# solenoid_final.net
KiCad netlist of a schematic drawn in EAGLE
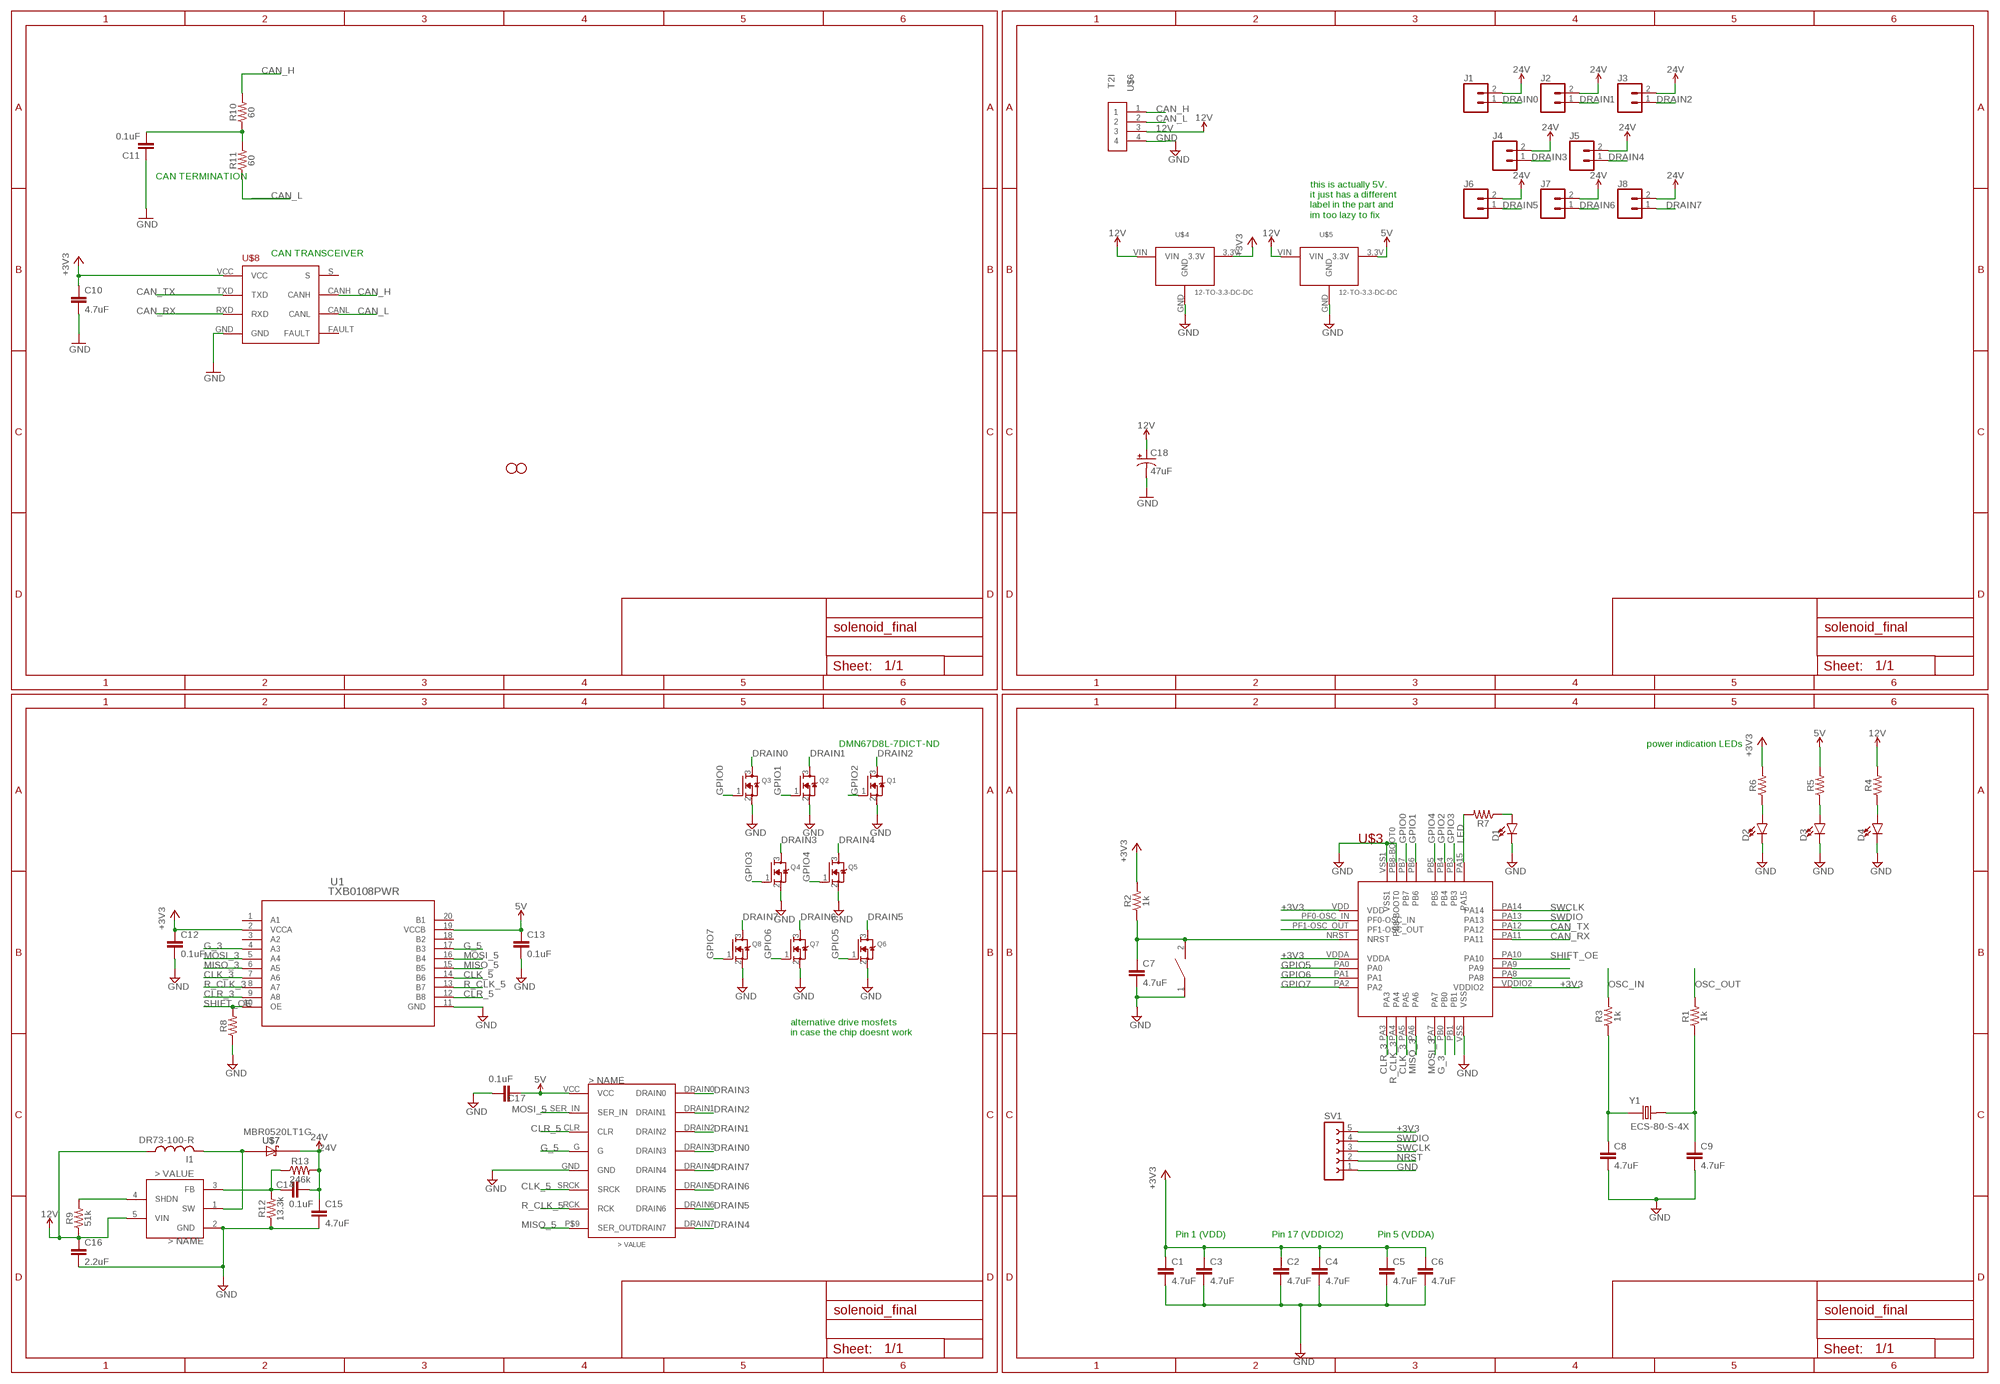
[diagram p0: schematic, sheet 1]

(export (version "E")
  (design (tool "Eeschema 10.0.6"))
  (components
    (comp (ref "C1")
      (value "4.7uF")
      (footprint "eagle-import:0603")
      (libsource (lib "eagle-import") (part "4.7UF0603"))
    )
    (comp (ref "C2")
      (value "4.7uF")
      (footprint "eagle-import:0603")
      (libsource (lib "eagle-import") (part "4.7UF0603"))
    )
    (comp (ref "C3")
      (value "4.7uF")
      (footprint "eagle-import:0603")
      (libsource (lib "eagle-import") (part "4.7UF0603"))
    )
    (comp (ref "C4")
      (value "4.7uF")
      (footprint "eagle-import:0603")
      (libsource (lib "eagle-import") (part "4.7UF0603"))
    )
    (comp (ref "C5")
      (value "4.7uF")
      (footprint "eagle-import:0603")
      (libsource (lib "eagle-import") (part "4.7UF0603"))
    )
    (comp (ref "C6")
      (value "4.7uF")
      (footprint "eagle-import:0603")
      (libsource (lib "eagle-import") (part "4.7UF0603"))
    )
    (comp (ref "C7")
      (value "4.7uF")
      (footprint "eagle-import:0603")
      (libsource (lib "eagle-import") (part "4.7UF0603"))
    )
    (comp (ref "C8")
      (value "4.7uF")
      (footprint "eagle-import:0603")
      (libsource (lib "eagle-import") (part "4.7UF0603"))
    )
    (comp (ref "C9")
      (value "4.7uF")
      (footprint "eagle-import:0603")
      (libsource (lib "eagle-import") (part "4.7UF0603"))
    )
    (comp (ref "C10")
      (value "4.7uF")
      (footprint "eagle-import:0603")
      (libsource (lib "eagle-import") (part "4.7UF0603"))
    )
    (comp (ref "C11")
      (value "0.1uF")
      (footprint "eagle-import:0603")
      (libsource (lib "eagle-import") (part "0.1UF-0603-25V-(+80/-20%)"))
    )
    (comp (ref "C12")
      (value "0.1uF")
      (footprint "eagle-import:0603")
      (libsource (lib "eagle-import") (part "0.1UF-0603-25V-5%"))
    )
    (comp (ref "C13")
      (value "0.1uF")
      (footprint "eagle-import:0603")
      (libsource (lib "eagle-import") (part "0.1UF-0603-25V-5%"))
    )
    (comp (ref "C14")
      (value "0.1uF")
      (footprint "eagle-import:0603")
      (libsource (lib "eagle-import") (part "0.1UF-0603-25V-5%"))
    )
    (comp (ref "C15")
      (value "4.7uF")
      (footprint "eagle-import:0603")
      (libsource (lib "eagle-import") (part "0.1UF-0603-25V-5%"))
    )
    (comp (ref "C16")
      (value "2.2uF")
      (footprint "eagle-import:0603")
      (libsource (lib "eagle-import") (part "0.1UF-0603-25V-5%"))
    )
    (comp (ref "C17")
      (value "0.1uF")
      (footprint "eagle-import:0603")
      (libsource (lib "eagle-import") (part "0.1UF-0603-25V-5%"))
    )
    (comp (ref "C18")
      (value "47uF")
      (footprint "eagle-import:PANASONIC_D")
      (libsource (lib "eagle-import") (part "47UF-POLAR-PANASONIC_D-35V-20%"))
    )
    (comp (ref "D1")
      (value "LED0603")
      (footprint "eagle-import:LED-0603")
      (libsource (lib "eagle-import") (part "LED0603"))
    )
    (comp (ref "D2")
      (value "LED0603")
      (footprint "eagle-import:LED-0603")
      (libsource (lib "eagle-import") (part "LED0603"))
    )
    (comp (ref "D3")
      (value "LED0603")
      (footprint "eagle-import:LED-0603")
      (libsource (lib "eagle-import") (part "LED0603"))
    )
    (comp (ref "D4")
      (value "LED0603")
      (footprint "eagle-import:LED-0603")
      (libsource (lib "eagle-import") (part "LED0603"))
    )
    (comp (ref "H1")
      (value "STAND-OFF")
      (footprint "eagle-import:STAND-OFF")
      (libsource (lib "eagle-import") (part "STAND-OFF"))
    )
    (comp (ref "H2")
      (value "STAND-OFF")
      (footprint "eagle-import:STAND-OFF")
      (libsource (lib "eagle-import") (part "STAND-OFF"))
    )
    (comp (ref "I1")
      (value "DR73-100-R")
      (footprint "eagle-import:DR73-100-R")
      (libsource (lib "eagle-import") (part "DR73-100-R"))
    )
    (comp (ref "J1")
      (value "CONN_02")
      (footprint "eagle-import:1X02")
      (libsource (lib "eagle-import") (part "CONN_02"))
    )
    (comp (ref "J2")
      (value "CONN_02")
      (footprint "eagle-import:1X02")
      (libsource (lib "eagle-import") (part "CONN_02"))
    )
    (comp (ref "J3")
      (value "CONN_02")
      (footprint "eagle-import:1X02")
      (libsource (lib "eagle-import") (part "CONN_02"))
    )
    (comp (ref "J4")
      (value "CONN_02")
      (footprint "eagle-import:1X02")
      (libsource (lib "eagle-import") (part "CONN_02"))
    )
    (comp (ref "J5")
      (value "CONN_02")
      (footprint "eagle-import:1X02")
      (libsource (lib "eagle-import") (part "CONN_02"))
    )
    (comp (ref "J6")
      (value "CONN_02")
      (footprint "eagle-import:1X02")
      (libsource (lib "eagle-import") (part "CONN_02"))
    )
    (comp (ref "J7")
      (value "CONN_02")
      (footprint "eagle-import:1X02")
      (libsource (lib "eagle-import") (part "CONN_02"))
    )
    (comp (ref "J8")
      (value "CONN_02")
      (footprint "eagle-import:1X02")
      (libsource (lib "eagle-import") (part "CONN_02"))
    )
    (comp (ref "Q1")
      (value "MOSFET-NWIDE")
      (footprint "eagle-import:SOT23-WIDE")
      (libsource (lib "eagle-import") (part "MOSFET-NWIDE"))
    )
    (comp (ref "Q2")
      (value "MOSFET-NWIDE")
      (footprint "eagle-import:SOT23-WIDE")
      (libsource (lib "eagle-import") (part "MOSFET-NWIDE"))
    )
    (comp (ref "Q3")
      (value "MOSFET-NWIDE")
      (footprint "eagle-import:SOT23-WIDE")
      (libsource (lib "eagle-import") (part "MOSFET-NWIDE"))
    )
    (comp (ref "Q4")
      (value "MOSFET-NWIDE")
      (footprint "eagle-import:SOT23-WIDE")
      (libsource (lib "eagle-import") (part "MOSFET-NWIDE"))
    )
    (comp (ref "Q5")
      (value "MOSFET-NWIDE")
      (footprint "eagle-import:SOT23-WIDE")
      (libsource (lib "eagle-import") (part "MOSFET-NWIDE"))
    )
    (comp (ref "Q6")
      (value "MOSFET-NWIDE")
      (footprint "eagle-import:SOT23-WIDE")
      (libsource (lib "eagle-import") (part "MOSFET-NWIDE"))
    )
    (comp (ref "Q7")
      (value "MOSFET-NWIDE")
      (footprint "eagle-import:SOT23-WIDE")
      (libsource (lib "eagle-import") (part "MOSFET-NWIDE"))
    )
    (comp (ref "Q8")
      (value "MOSFET-NWIDE")
      (footprint "eagle-import:SOT23-WIDE")
      (libsource (lib "eagle-import") (part "MOSFET-NWIDE"))
    )
    (comp (ref "R1")
      (value "1k")
      (footprint "eagle-import:0603")
      (libsource (lib "eagle-import") (part "1KOHM-0603-1/10W-1%"))
    )
    (comp (ref "R2")
      (value "1k")
      (footprint "eagle-import:0603")
      (libsource (lib "eagle-import") (part "1KOHM-0603-1/10W-1%"))
    )
    (comp (ref "R3")
      (value "1k")
      (footprint "eagle-import:0603")
      (libsource (lib "eagle-import") (part "1KOHM-0603-1/10W-1%"))
    )
    (comp (ref "R4")
      (value "RESISTOR0603")
      (footprint "eagle-import:0603")
      (libsource (lib "eagle-import") (part "RESISTOR0603"))
    )
    (comp (ref "R5")
      (value "RESISTOR0603")
      (footprint "eagle-import:0603")
      (libsource (lib "eagle-import") (part "RESISTOR0603"))
    )
    (comp (ref "R6")
      (value "RESISTOR0603")
      (footprint "eagle-import:0603")
      (libsource (lib "eagle-import") (part "RESISTOR0603"))
    )
    (comp (ref "R7")
      (value "RESISTOR0603")
      (footprint "eagle-import:0603")
      (libsource (lib "eagle-import") (part "RESISTOR0603"))
    )
    (comp (ref "R8")
      (value "RESISTOR0603")
      (footprint "eagle-import:0603")
      (libsource (lib "eagle-import") (part "RESISTOR0603"))
    )
    (comp (ref "R9")
      (value "51k")
      (footprint "eagle-import:0603")
      (libsource (lib "eagle-import") (part "RESISTOR0603"))
    )
    (comp (ref "R10")
      (value "60")
      (footprint "eagle-import:0603")
      (libsource (lib "eagle-import") (part "1KOHM-0603-1/10W-1%"))
    )
    (comp (ref "R11")
      (value "60")
      (footprint "eagle-import:0603")
      (libsource (lib "eagle-import") (part "1KOHM-0603-1/10W-1%"))
    )
    (comp (ref "R12")
      (value "13.3k")
      (footprint "eagle-import:0603")
      (libsource (lib "eagle-import") (part "RESISTOR0603"))
    )
    (comp (ref "R13")
      (value "246k")
      (footprint "eagle-import:0603")
      (libsource (lib "eagle-import") (part "RESISTOR0603"))
    )
    (comp (ref "RESET")
      (value "SWITCH")
      (footprint "eagle-import:SW_2512")
      (libsource (lib "eagle-import") (part "SWITCH"))
    )
    (comp (ref "SV1")
      (value "FE05-1")
      (footprint "eagle-import:FE05-1")
      (libsource (lib "eagle-import") (part "FE05-1"))
    )
    (comp (ref "U$1")
      (value "SHIFT_REGISTER")
      (footprint "eagle-import:SHIFT_REGISTER")
      (libsource (lib "eagle-import") (part "SHIFT_REGISTER"))
    )
    (comp (ref "U$2")
      (value "LM27313")
      (footprint "eagle-import:SOT95P300X145-5")
      (libsource (lib "eagle-import") (part "LM27313"))
    )
    (comp (ref "U$3")
      (value "STM32F042K6T6")
      (footprint "eagle-import:STM32F042K6T6")
      (libsource (lib "eagle-import") (part "STM32F042K6T6"))
    )
    (comp (ref "U$4")
      (value "12-TO-3.3-DC-DC")
      (footprint "eagle-import:MURATA-DCDC")
      (libsource (lib "eagle-import") (part "12-TO-3.3-DC-DC"))
    )
    (comp (ref "U$5")
      (value "12-TO-3.3-DC-DC")
      (footprint "eagle-import:MURATA-DCDC")
      (libsource (lib "eagle-import") (part "12-TO-3.3-DC-DC"))
    )
    (comp (ref "U$6")
      (value "T2I")
      (footprint "eagle-import:T2I")
      (libsource (lib "eagle-import") (part "T2I"))
    )
    (comp (ref "U$7")
      (value "MBR0520LT1G")
      (footprint "eagle-import:SOD3716X135")
      (libsource (lib "eagle-import") (part "MBR0520LT1G"))
    )
    (comp (ref "U$8")
      (value "TCAN337D")
      (footprint "eagle-import:TCAN337D")
      (libsource (lib "eagle-import") (part "TCAN337D"))
    )
    (comp (ref "U1")
      (value "TXB0108PWR")
      (footprint "eagle-import:PW20")
      (libsource (lib "eagle-import") (part "TXB0108PWR"))
    )
    (comp (ref "Y1")
      (value "ECS-80-S-4X")
      (footprint "eagle-import:XTAL_ECS-80-S-4X")
      (fields (field (name "DIGI-KEY_PART_NUMBER") "X1057-ND") (field (name "MF") "ECS International"))
      (libsource (lib "eagle-import") (part "ECS-80-S-4X"))
    )
  )
  (nets
    (net (code "1") (name "+3V3") (class "Default")
      (node (ref "C1") (pin "1") (pinfunction "1_1") (pintype "passive"))
      (node (ref "C10") (pin "1") (pinfunction "1_1") (pintype "passive"))
      (node (ref "C12") (pin "1") (pinfunction "1_1") (pintype "passive"))
      (node (ref "C2") (pin "1") (pinfunction "1_1") (pintype "passive"))
      (node (ref "C3") (pin "1") (pinfunction "1_1") (pintype "passive"))
      (node (ref "C4") (pin "1") (pinfunction "1_1") (pintype "passive"))
      (node (ref "C5") (pin "1") (pinfunction "1_1") (pintype "passive"))
      (node (ref "C6") (pin "1") (pinfunction "1_1") (pintype "passive"))
      (node (ref "R2") (pin "2") (pinfunction "2_2") (pintype "passive"))
      (node (ref "R6") (pin "2") (pinfunction "2_2") (pintype "passive"))
      (node (ref "SV1") (pin "5") (pinfunction "5_5") (pintype "passive"))
      (node (ref "U$3") (pin "VDD") (pinfunction "VDD_VDD") (pintype "bidirectional"))
      (node (ref "U$3") (pin "VDDA") (pinfunction "VDDA_VDDA") (pintype "bidirectional"))
      (node (ref "U$3") (pin "VDDIO2") (pinfunction "VDDIO2_VDDIO2") (pintype "bidirectional"))
      (node (ref "U$4") (pin "3.3V") (pinfunction "3.3V_3.3V") (pintype "bidirectional"))
      (node (ref "U$8") (pin "VCC") (pinfunction "VCC_VCC") (pintype "bidirectional"))
      (node (ref "U1") (pin "2") (pinfunction "VCCA_2") (pintype "power_in"))
    )
    (net (code "2") (name "/CAN_H") (class "Default")
      (node (ref "R10") (pin "2") (pinfunction "2_2") (pintype "passive"))
      (node (ref "U$6") (pin "1") (pinfunction "1_1") (pintype "bidirectional"))
      (node (ref "U$8") (pin "CANH") (pinfunction "CANH_CANH") (pintype "bidirectional"))
    )
    (net (code "3") (name "/CAN_L") (class "Default")
      (node (ref "R11") (pin "1") (pinfunction "1_1") (pintype "passive"))
      (node (ref "U$6") (pin "2") (pinfunction "2_2") (pintype "bidirectional"))
      (node (ref "U$8") (pin "CANL") (pinfunction "CANL_CANL") (pintype "bidirectional"))
    )
    (net (code "4") (name "/CAN_RX") (class "Default")
      (node (ref "U$3") (pin "PA11") (pinfunction "PA11_PA11") (pintype "bidirectional"))
      (node (ref "U$8") (pin "RXD") (pinfunction "RXD_RXD") (pintype "bidirectional"))
    )
    (net (code "5") (name "/CAN_TX") (class "Default")
      (node (ref "U$3") (pin "PA12") (pinfunction "PA12_PA12") (pintype "bidirectional"))
      (node (ref "U$8") (pin "TXD") (pinfunction "TXD_TXD") (pintype "bidirectional"))
    )
    (net (code "6") (name "/CLK_3") (class "Default")
      (node (ref "U$3") (pin "PA5") (pinfunction "PA5_PA5") (pintype "bidirectional"))
      (node (ref "U1") (pin "7") (pinfunction "A6_7") (pintype "bidirectional"))
    )
    (net (code "7") (name "/CLK_5") (class "Default")
      (node (ref "U$1") (pin "SRCK") (pinfunction "SRCK_SRCK") (pintype "bidirectional"))
      (node (ref "U1") (pin "14") (pinfunction "B6_14") (pintype "bidirectional"))
    )
    (net (code "8") (name "/CLR_3") (class "Default")
      (node (ref "U$3") (pin "PA3") (pinfunction "PA3_PA3") (pintype "bidirectional"))
      (node (ref "U1") (pin "9") (pinfunction "A8_9") (pintype "bidirectional"))
    )
    (net (code "9") (name "/CLR_5") (class "Default")
      (node (ref "U$1") (pin "CLR") (pinfunction "CLR_CLR") (pintype "bidirectional"))
      (node (ref "U1") (pin "12") (pinfunction "B8_12") (pintype "bidirectional"))
    )
    (net (code "10") (name "/DRAIN0") (class "Default")
      (node (ref "J1") (pin "1") (pinfunction "1_1") (pintype "passive"))
      (node (ref "Q3") (pin "3") (pinfunction "D_3") (pintype "bidirectional"))
      (node (ref "U$1") (pin "DRAIN3") (pinfunction "DRAIN3_DRAIN3") (pintype "bidirectional"))
    )
    (net (code "11") (name "/DRAIN1") (class "Default")
      (node (ref "J2") (pin "1") (pinfunction "1_1") (pintype "passive"))
      (node (ref "Q2") (pin "3") (pinfunction "D_3") (pintype "bidirectional"))
      (node (ref "U$1") (pin "DRAIN2") (pinfunction "DRAIN2_DRAIN2") (pintype "bidirectional"))
    )
    (net (code "12") (name "/DRAIN2") (class "Default")
      (node (ref "J3") (pin "1") (pinfunction "1_1") (pintype "passive"))
      (node (ref "Q1") (pin "3") (pinfunction "D_3") (pintype "bidirectional"))
      (node (ref "U$1") (pin "DRAIN1") (pinfunction "DRAIN1_DRAIN1") (pintype "bidirectional"))
    )
    (net (code "13") (name "/DRAIN3") (class "Default")
      (node (ref "J4") (pin "1") (pinfunction "1_1") (pintype "passive"))
      (node (ref "Q4") (pin "3") (pinfunction "D_3") (pintype "bidirectional"))
      (node (ref "U$1") (pin "DRAIN0") (pinfunction "DRAIN0_DRAIN0") (pintype "bidirectional"))
    )
    (net (code "14") (name "/DRAIN4") (class "Default")
      (node (ref "J5") (pin "1") (pinfunction "1_1") (pintype "passive"))
      (node (ref "Q5") (pin "3") (pinfunction "D_3") (pintype "bidirectional"))
      (node (ref "U$1") (pin "DRAIN7") (pinfunction "DRAIN7_DRAIN7") (pintype "bidirectional"))
    )
    (net (code "15") (name "/DRAIN5") (class "Default")
      (node (ref "J6") (pin "1") (pinfunction "1_1") (pintype "passive"))
      (node (ref "Q6") (pin "3") (pinfunction "D_3") (pintype "bidirectional"))
      (node (ref "U$1") (pin "DRAIN6") (pinfunction "DRAIN6_DRAIN6") (pintype "bidirectional"))
    )
    (net (code "16") (name "/DRAIN6") (class "Default")
      (node (ref "J7") (pin "1") (pinfunction "1_1") (pintype "passive"))
      (node (ref "Q7") (pin "3") (pinfunction "D_3") (pintype "bidirectional"))
      (node (ref "U$1") (pin "DRAIN5") (pinfunction "DRAIN5_DRAIN5") (pintype "bidirectional"))
    )
    (net (code "17") (name "/DRAIN7") (class "Default")
      (node (ref "J8") (pin "1") (pinfunction "1_1") (pintype "passive"))
      (node (ref "Q8") (pin "3") (pinfunction "D_3") (pintype "bidirectional"))
      (node (ref "U$1") (pin "DRAIN4") (pinfunction "DRAIN4_DRAIN4") (pintype "bidirectional"))
    )
    (net (code "18") (name "/GPIO0") (class "Default")
      (node (ref "Q3") (pin "1") (pinfunction "G_1") (pintype "bidirectional"))
      (node (ref "U$3") (pin "PB7") (pinfunction "PB7_PB7") (pintype "bidirectional"))
    )
    (net (code "19") (name "/GPIO1") (class "Default")
      (node (ref "Q2") (pin "1") (pinfunction "G_1") (pintype "bidirectional"))
      (node (ref "U$3") (pin "PB6") (pinfunction "PB6_PB6") (pintype "bidirectional"))
    )
    (net (code "20") (name "/GPIO2") (class "Default")
      (node (ref "Q1") (pin "1") (pinfunction "G_1") (pintype "bidirectional"))
      (node (ref "U$3") (pin "PB4") (pinfunction "PB4_PB4") (pintype "bidirectional"))
    )
    (net (code "21") (name "/GPIO3") (class "Default")
      (node (ref "Q4") (pin "1") (pinfunction "G_1") (pintype "bidirectional"))
      (node (ref "U$3") (pin "PB3") (pinfunction "PB3_PB3") (pintype "bidirectional"))
    )
    (net (code "22") (name "/GPIO4") (class "Default")
      (node (ref "Q5") (pin "1") (pinfunction "G_1") (pintype "bidirectional"))
      (node (ref "U$3") (pin "PB5") (pinfunction "PB5_PB5") (pintype "bidirectional"))
    )
    (net (code "23") (name "/GPIO5") (class "Default")
      (node (ref "Q6") (pin "1") (pinfunction "G_1") (pintype "bidirectional"))
      (node (ref "U$3") (pin "PA0") (pinfunction "PA0_PA0") (pintype "bidirectional"))
    )
    (net (code "24") (name "/GPIO6") (class "Default")
      (node (ref "Q7") (pin "1") (pinfunction "G_1") (pintype "bidirectional"))
      (node (ref "U$3") (pin "PA1") (pinfunction "PA1_PA1") (pintype "bidirectional"))
    )
    (net (code "25") (name "/GPIO7") (class "Default")
      (node (ref "Q8") (pin "1") (pinfunction "G_1") (pintype "bidirectional"))
      (node (ref "U$3") (pin "PA2") (pinfunction "PA2_PA2") (pintype "bidirectional"))
    )
    (net (code "26") (name "/G_3") (class "Default")
      (node (ref "U$3") (pin "PB0") (pinfunction "PB0_PB0") (pintype "bidirectional"))
      (node (ref "U1") (pin "4") (pinfunction "A3_4") (pintype "bidirectional"))
    )
    (net (code "27") (name "/G_5") (class "Default")
      (node (ref "U$1") (pin "G") (pinfunction "G_G") (pintype "bidirectional"))
      (node (ref "U1") (pin "17") (pinfunction "B3_17") (pintype "bidirectional"))
    )
    (net (code "28") (name "/LED") (class "Default")
      (node (ref "R7") (pin "2") (pinfunction "2_2") (pintype "passive"))
      (node (ref "U$3") (pin "PA15") (pinfunction "PA15_PA15") (pintype "bidirectional"))
    )
    (net (code "29") (name "/MISO_3") (class "Default")
      (node (ref "U$3") (pin "PA6") (pinfunction "PA6_PA6") (pintype "bidirectional"))
      (node (ref "U1") (pin "6") (pinfunction "A5_6") (pintype "bidirectional"))
    )
    (net (code "30") (name "/MISO_5") (class "Default")
      (node (ref "U$1") (pin "P$9") (pinfunction "SER_OUT_P$9") (pintype "bidirectional"))
      (node (ref "U1") (pin "15") (pinfunction "B5_15") (pintype "bidirectional"))
    )
    (net (code "31") (name "/MOSI_3") (class "Default")
      (node (ref "U$3") (pin "PA7") (pinfunction "PA7_PA7") (pintype "bidirectional"))
      (node (ref "U1") (pin "5") (pinfunction "A4_5") (pintype "bidirectional"))
    )
    (net (code "32") (name "/MOSI_5") (class "Default")
      (node (ref "U$1") (pin "SER_IN") (pinfunction "SER_IN_SER_IN") (pintype "bidirectional"))
      (node (ref "U1") (pin "16") (pinfunction "B4_16") (pintype "bidirectional"))
    )
    (net (code "33") (name "/NRST") (class "Default")
      (node (ref "C7") (pin "1") (pinfunction "1_1") (pintype "passive"))
      (node (ref "R2") (pin "1") (pinfunction "1_1") (pintype "passive"))
      (node (ref "RESET") (pin "2") (pinfunction "P$2_2") (pintype "bidirectional"))
      (node (ref "SV1") (pin "2") (pinfunction "2_2") (pintype "passive"))
      (node (ref "U$3") (pin "NRST") (pinfunction "NRST_NRST") (pintype "bidirectional"))
    )
    (net (code "34") (name "/OSC_IN") (class "Default")
      (node (ref "R3") (pin "2") (pinfunction "2_2") (pintype "passive"))
      (node (ref "U$3") (pin "PF0-OSC_IN") (pinfunction "PF0-OSC_IN_PF0-OSC_IN") (pintype "bidirectional"))
    )
    (net (code "35") (name "/OSC_OUT") (class "Default")
      (node (ref "R1") (pin "2") (pinfunction "2_2") (pintype "passive"))
      (node (ref "U$3") (pin "PF1-OSC_OUT") (pinfunction "PF1-OSC_OUT_PF1-OSC_OUT") (pintype "bidirectional"))
    )
    (net (code "36") (name "/R_CLK_3") (class "Default")
      (node (ref "U$3") (pin "PA4") (pinfunction "PA4_PA4") (pintype "bidirectional"))
      (node (ref "U1") (pin "8") (pinfunction "A7_8") (pintype "bidirectional"))
    )
    (net (code "37") (name "/R_CLK_5") (class "Default")
      (node (ref "U$1") (pin "RCK") (pinfunction "RCK_RCK") (pintype "bidirectional"))
      (node (ref "U1") (pin "13") (pinfunction "B7_13") (pintype "bidirectional"))
    )
    (net (code "38") (name "/SHIFT_OE") (class "Default")
      (node (ref "R8") (pin "2") (pinfunction "2_2") (pintype "passive"))
      (node (ref "U$3") (pin "PA10") (pinfunction "PA10_PA10") (pintype "bidirectional"))
      (node (ref "U1") (pin "10") (pinfunction "OE_10") (pintype "bidirectional"))
    )
    (net (code "39") (name "/SWCLK") (class "Default")
      (node (ref "SV1") (pin "3") (pinfunction "3_3") (pintype "passive"))
      (node (ref "U$3") (pin "PA14") (pinfunction "PA14_PA14") (pintype "bidirectional"))
    )
    (net (code "40") (name "/SWDIO") (class "Default")
      (node (ref "SV1") (pin "4") (pinfunction "4_4") (pintype "passive"))
      (node (ref "U$3") (pin "PA13") (pinfunction "PA13_PA13") (pintype "bidirectional"))
    )
    (net (code "41") (name "5V") (class "Default")
      (node (ref "C13") (pin "1") (pinfunction "1_1") (pintype "passive"))
      (node (ref "C17") (pin "1") (pinfunction "1_1") (pintype "passive"))
      (node (ref "R5") (pin "2") (pinfunction "2_2") (pintype "passive"))
      (node (ref "U$1") (pin "VCC") (pinfunction "VCC_VCC") (pintype "bidirectional"))
      (node (ref "U$5") (pin "3.3V") (pinfunction "3.3V_3.3V") (pintype "bidirectional"))
      (node (ref "U1") (pin "19") (pinfunction "VCCB_19") (pintype "power_in"))
    )
    (net (code "42") (name "12V") (class "Default")
      (node (ref "C16") (pin "1") (pinfunction "1_1") (pintype "passive"))
      (node (ref "C18") (pin "+") (pinfunction "+_+") (pintype "passive"))
      (node (ref "I1") (pin "1") (pinfunction "1_1") (pintype "passive"))
      (node (ref "R4") (pin "2") (pinfunction "2_2") (pintype "passive"))
      (node (ref "R9") (pin "1") (pinfunction "1_1") (pintype "passive"))
      (node (ref "U$2") (pin "5") (pinfunction "VIN_5") (pintype "bidirectional"))
      (node (ref "U$4") (pin "VIN") (pinfunction "VIN_VIN") (pintype "bidirectional"))
      (node (ref "U$5") (pin "VIN") (pinfunction "VIN_VIN") (pintype "bidirectional"))
      (node (ref "U$6") (pin "3") (pinfunction "3_3") (pintype "bidirectional"))
    )
    (net (code "43") (name "24V") (class "Default")
      (node (ref "C14") (pin "2") (pinfunction "2_2") (pintype "passive"))
      (node (ref "C15") (pin "1") (pinfunction "1_1") (pintype "passive"))
      (node (ref "J1") (pin "2") (pinfunction "2_2") (pintype "passive"))
      (node (ref "J2") (pin "2") (pinfunction "2_2") (pintype "passive"))
      (node (ref "J3") (pin "2") (pinfunction "2_2") (pintype "passive"))
      (node (ref "J4") (pin "2") (pinfunction "2_2") (pintype "passive"))
      (node (ref "J5") (pin "2") (pinfunction "2_2") (pintype "passive"))
      (node (ref "J6") (pin "2") (pinfunction "2_2") (pintype "passive"))
      (node (ref "J7") (pin "2") (pinfunction "2_2") (pintype "passive"))
      (node (ref "J8") (pin "2") (pinfunction "2_2") (pintype "passive"))
      (node (ref "R13") (pin "2") (pinfunction "2_2") (pintype "passive"))
      (node (ref "U$7") (pin "2") (pinfunction "C_2") (pintype "passive"))
    )
    (net (code "44") (name "GND") (class "Default")
      (node (ref "C1") (pin "2") (pinfunction "2_2") (pintype "passive"))
      (node (ref "C10") (pin "2") (pinfunction "2_2") (pintype "passive"))
      (node (ref "C11") (pin "1") (pinfunction "1_1") (pintype "passive"))
      (node (ref "C12") (pin "2") (pinfunction "2_2") (pintype "passive"))
      (node (ref "C13") (pin "2") (pinfunction "2_2") (pintype "passive"))
      (node (ref "C15") (pin "2") (pinfunction "2_2") (pintype "passive"))
      (node (ref "C16") (pin "2") (pinfunction "2_2") (pintype "passive"))
      (node (ref "C17") (pin "2") (pinfunction "2_2") (pintype "passive"))
      (node (ref "C18") (pin "-") (pinfunction "-_-") (pintype "passive"))
      (node (ref "C2") (pin "2") (pinfunction "2_2") (pintype "passive"))
      (node (ref "C3") (pin "2") (pinfunction "2_2") (pintype "passive"))
      (node (ref "C4") (pin "2") (pinfunction "2_2") (pintype "passive"))
      (node (ref "C5") (pin "2") (pinfunction "2_2") (pintype "passive"))
      (node (ref "C6") (pin "2") (pinfunction "2_2") (pintype "passive"))
      (node (ref "C7") (pin "2") (pinfunction "2_2") (pintype "passive"))
      (node (ref "C8") (pin "2") (pinfunction "2_2") (pintype "passive"))
      (node (ref "C9") (pin "2") (pinfunction "2_2") (pintype "passive"))
      (node (ref "D1") (pin "C") (pinfunction "C_C") (pintype "passive"))
      (node (ref "D2") (pin "C") (pinfunction "C_C") (pintype "passive"))
      (node (ref "D3") (pin "C") (pinfunction "C_C") (pintype "passive"))
      (node (ref "D4") (pin "C") (pinfunction "C_C") (pintype "passive"))
      (node (ref "Q1") (pin "2") (pinfunction "S_2") (pintype "bidirectional"))
      (node (ref "Q2") (pin "2") (pinfunction "S_2") (pintype "bidirectional"))
      (node (ref "Q3") (pin "2") (pinfunction "S_2") (pintype "bidirectional"))
      (node (ref "Q4") (pin "2") (pinfunction "S_2") (pintype "bidirectional"))
      (node (ref "Q5") (pin "2") (pinfunction "S_2") (pintype "bidirectional"))
      (node (ref "Q6") (pin "2") (pinfunction "S_2") (pintype "bidirectional"))
      (node (ref "Q7") (pin "2") (pinfunction "S_2") (pintype "bidirectional"))
      (node (ref "Q8") (pin "2") (pinfunction "S_2") (pintype "bidirectional"))
      (node (ref "R12") (pin "1") (pinfunction "1_1") (pintype "passive"))
      (node (ref "R8") (pin "1") (pinfunction "1_1") (pintype "passive"))
      (node (ref "RESET") (pin "1") (pinfunction "P$1_1") (pintype "bidirectional"))
      (node (ref "SV1") (pin "1") (pinfunction "1_1") (pintype "passive"))
      (node (ref "U$1") (pin "GND") (pinfunction "GND_GND") (pintype "bidirectional"))
      (node (ref "U$2") (pin "2") (pinfunction "GND_2") (pintype "bidirectional"))
      (node (ref "U$3") (pin "PB8-BOOT0") (pinfunction "PB8-BOOT0_PB8-BOOT0") (pintype "bidirectional"))
      (node (ref "U$3") (pin "VSS") (pinfunction "VSS_VSS") (pintype "bidirectional"))
      (node (ref "U$3") (pin "VSS1") (pinfunction "VSS1_VSS1") (pintype "bidirectional"))
      (node (ref "U$4") (pin "GND") (pinfunction "GND_GND") (pintype "bidirectional"))
      (node (ref "U$5") (pin "GND") (pinfunction "GND_GND") (pintype "bidirectional"))
      (node (ref "U$6") (pin "4") (pinfunction "4_4") (pintype "bidirectional"))
      (node (ref "U$8") (pin "GND") (pinfunction "GND_GND") (pintype "bidirectional"))
      (node (ref "U1") (pin "11") (pinfunction "GND_11") (pintype "power_in"))
    )
    (net (code "45") (name "Net-(C8-Pad1)") (class "Default")
      (node (ref "C8") (pin "1") (pinfunction "1_1") (pintype "passive"))
      (node (ref "R3") (pin "1") (pinfunction "1_1") (pintype "passive"))
      (node (ref "Y1") (pin "1") (pinfunction "1_1") (pintype "passive"))
    )
    (net (code "46") (name "Net-(C9-Pad1)") (class "Default")
      (node (ref "C9") (pin "1") (pinfunction "1_1") (pintype "passive"))
      (node (ref "R1") (pin "1") (pinfunction "1_1") (pintype "passive"))
      (node (ref "Y1") (pin "2") (pinfunction "2_2") (pintype "passive"))
    )
    (net (code "47") (name "Net-(C11-Pad2)") (class "Default")
      (node (ref "C11") (pin "2") (pinfunction "2_2") (pintype "passive"))
      (node (ref "R10") (pin "1") (pinfunction "1_1") (pintype "passive"))
      (node (ref "R11") (pin "2") (pinfunction "2_2") (pintype "passive"))
    )
    (net (code "48") (name "Net-(D1-PadA)") (class "Default")
      (node (ref "D1") (pin "A") (pinfunction "A_A") (pintype "passive"))
      (node (ref "R7") (pin "1") (pinfunction "1_1") (pintype "passive"))
    )
    (net (code "49") (name "Net-(D2-PadA)") (class "Default")
      (node (ref "D2") (pin "A") (pinfunction "A_A") (pintype "passive"))
      (node (ref "R6") (pin "1") (pinfunction "1_1") (pintype "passive"))
    )
    (net (code "50") (name "Net-(D3-PadA)") (class "Default")
      (node (ref "D3") (pin "A") (pinfunction "A_A") (pintype "passive"))
      (node (ref "R5") (pin "1") (pinfunction "1_1") (pintype "passive"))
    )
    (net (code "51") (name "Net-(D4-PadA)") (class "Default")
      (node (ref "D4") (pin "A") (pinfunction "A_A") (pintype "passive"))
      (node (ref "R4") (pin "1") (pinfunction "1_1") (pintype "passive"))
    )
    (net (code "52") (name "Net-(U$2-FB)") (class "Default")
      (node (ref "C14") (pin "1") (pinfunction "1_1") (pintype "passive"))
      (node (ref "R12") (pin "2") (pinfunction "2_2") (pintype "passive"))
      (node (ref "R13") (pin "1") (pinfunction "1_1") (pintype "passive"))
      (node (ref "U$2") (pin "3") (pinfunction "FB_3") (pintype "bidirectional"))
    )
    (net (code "53") (name "Net-(U$2-SHDN)") (class "Default")
      (node (ref "R9") (pin "2") (pinfunction "2_2") (pintype "passive"))
      (node (ref "U$2") (pin "4") (pinfunction "SHDN_4") (pintype "bidirectional"))
    )
    (net (code "54") (name "Net-(U$2-SW)") (class "Default")
      (node (ref "I1") (pin "2") (pinfunction "2_2") (pintype "passive"))
      (node (ref "U$2") (pin "1") (pinfunction "SW_1") (pintype "bidirectional"))
      (node (ref "U$7") (pin "1") (pinfunction "A_1") (pintype "passive"))
    )
    (net (code "55") (name "unconnected-(U$3-PadPA8)") (class "Default")
      (node (ref "U$3") (pin "PA8") (pinfunction "PA8_PA8") (pintype "bidirectional"))
    )
    (net (code "56") (name "unconnected-(U$3-PadPA9)") (class "Default")
      (node (ref "U$3") (pin "PA9") (pinfunction "PA9_PA9") (pintype "bidirectional"))
    )
    (net (code "57") (name "unconnected-(U$3-PadPB1)") (class "Default")
      (node (ref "U$3") (pin "PB1") (pinfunction "PB1_PB1") (pintype "bidirectional"))
    )
    (net (code "58") (name "unconnected-(U$8-PadFAULT)") (class "Default")
      (node (ref "U$8") (pin "FAULT") (pinfunction "FAULT_FAULT") (pintype "bidirectional"))
    )
    (net (code "59") (name "unconnected-(U$8-PadS)") (class "Default")
      (node (ref "U$8") (pin "S") (pinfunction "S_S") (pintype "bidirectional"))
    )
    (net (code "60") (name "unconnected-(U1-A1-Pad1)") (class "Default")
      (node (ref "U1") (pin "1") (pinfunction "A1_1") (pintype "bidirectional"))
    )
    (net (code "61") (name "unconnected-(U1-A2-Pad3)") (class "Default")
      (node (ref "U1") (pin "3") (pinfunction "A2_3") (pintype "bidirectional"))
    )
    (net (code "62") (name "unconnected-(U1-B1-Pad20)") (class "Default")
      (node (ref "U1") (pin "20") (pinfunction "B1_20") (pintype "bidirectional"))
    )
    (net (code "63") (name "unconnected-(U1-B2-Pad18)") (class "Default")
      (node (ref "U1") (pin "18") (pinfunction "B2_18") (pintype "bidirectional"))
    )
  )
)
